# Xiao-SCD41-SSD1306.net
KiCad netlist of a schematic drawn in EAGLE
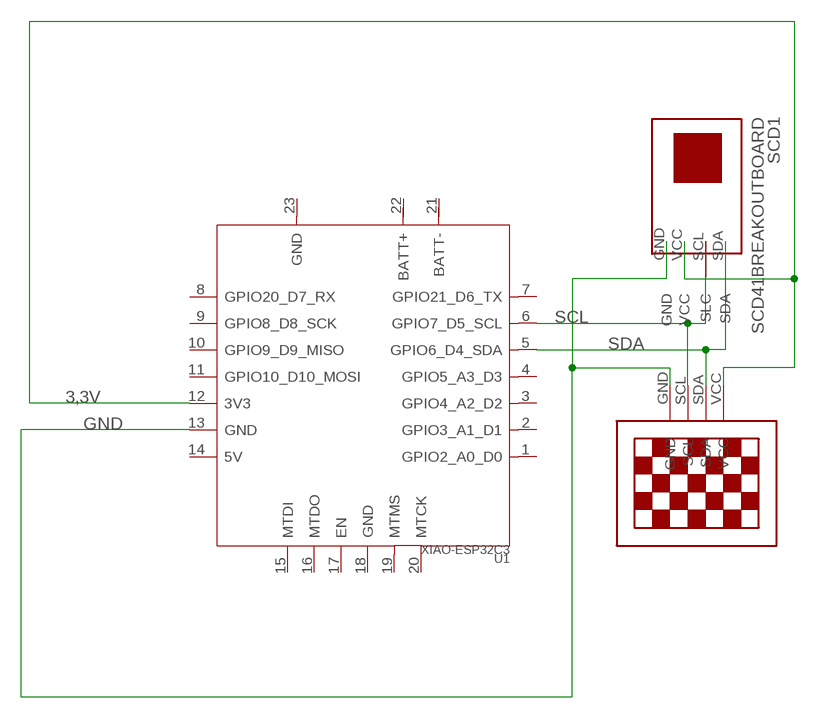
[diagram p0: schematic, sheet 1]

(export (version "E")
  (design (tool "Eeschema 10.0.6"))
  (components
    (comp (ref "SCD1")
      (value "SCD41BREAKOUTBOARD")
      (footprint "eagle-import:SCD41")
      (libsource (lib "eagle-import") (part "SCD41BREAKOUTBOARD"))
    )
    (comp (ref "U$1")
      (value "13\"OLED13\"OLED")
      (footprint "eagle-import:1.3_OLED")
      (libsource (lib "eagle-import") (part "13{dblquote}OLED13{dblquote}OLED"))
    )
    (comp (ref "U1")
      (value "XIAO-ESP32C3")
      (footprint "eagle-import:XIAO-ESP32C3-MODULE14P-2.54-21X17.8MM")
      (libsource (lib "eagle-import") (part "XIAO-ESP32C3"))
    )
  )
  (nets
    (net (code "1") (name "/3,3V") (class "Default")
      (node (ref "SCD1") (pin "VCC") (pinfunction "VCC_VCC") (pintype "bidirectional"))
      (node (ref "U$1") (pin "VCC") (pinfunction "VCC_VCC") (pintype "bidirectional"))
      (node (ref "U1") (pin "12") (pinfunction "3V3_12") (pintype "bidirectional"))
    )
    (net (code "2") (name "/GND") (class "Default")
      (node (ref "SCD1") (pin "GND") (pinfunction "GND_GND") (pintype "bidirectional"))
      (node (ref "U$1") (pin "GND") (pinfunction "GND_GND") (pintype "bidirectional"))
      (node (ref "U1") (pin "13") (pinfunction "GND_13") (pintype "bidirectional"))
    )
    (net (code "3") (name "/SCL") (class "Default")
      (node (ref "SCD1") (pin "SCL") (pinfunction "SLC_SCL") (pintype "bidirectional"))
      (node (ref "U$1") (pin "SCL") (pinfunction "SCL_SCL") (pintype "bidirectional"))
      (node (ref "U1") (pin "6") (pinfunction "GPIO7_D5_SCL_6") (pintype "bidirectional"))
    )
    (net (code "4") (name "/SDA") (class "Default")
      (node (ref "SCD1") (pin "SDA") (pinfunction "SDA_SDA") (pintype "bidirectional"))
      (node (ref "U$1") (pin "SDA") (pinfunction "SDA_SDA") (pintype "bidirectional"))
      (node (ref "U1") (pin "5") (pinfunction "GPIO6_D4_SDA_5") (pintype "bidirectional"))
    )
    (net (code "5") (name "unconnected-(U1-5V-Pad14)") (class "Default")
      (node (ref "U1") (pin "14") (pinfunction "5V_14") (pintype "bidirectional"))
    )
    (net (code "6") (name "unconnected-(U1-BATT+-Pad22)") (class "Default")
      (node (ref "U1") (pin "22") (pinfunction "BATT+_22") (pintype "bidirectional"))
    )
    (net (code "7") (name "unconnected-(U1-BATT--Pad21)") (class "Default")
      (node (ref "U1") (pin "21") (pinfunction "BATT-_21") (pintype "bidirectional"))
    )
    (net (code "8") (name "unconnected-(U1-EN-Pad17)") (class "Default")
      (node (ref "U1") (pin "17") (pinfunction "EN_17") (pintype "bidirectional"))
    )
    (net (code "9") (name "unconnected-(U1-GND-Pad18)") (class "Default")
      (node (ref "U1") (pin "18") (pinfunction "GND_18") (pintype "bidirectional"))
    )
    (net (code "10") (name "unconnected-(U1-GND-Pad23)") (class "Default")
      (node (ref "U1") (pin "23") (pinfunction "GND_23") (pintype "bidirectional"))
    )
    (net (code "11") (name "unconnected-(U1-GPIO2_A0_D0-Pad1)") (class "Default")
      (node (ref "U1") (pin "1") (pinfunction "GPIO2_A0_D0_1") (pintype "bidirectional"))
    )
    (net (code "12") (name "unconnected-(U1-GPIO3_A1_D1-Pad2)") (class "Default")
      (node (ref "U1") (pin "2") (pinfunction "GPIO3_A1_D1_2") (pintype "bidirectional"))
    )
    (net (code "13") (name "unconnected-(U1-GPIO4_A2_D2-Pad3)") (class "Default")
      (node (ref "U1") (pin "3") (pinfunction "GPIO4_A2_D2_3") (pintype "bidirectional"))
    )
    (net (code "14") (name "unconnected-(U1-GPIO5_A3_D3-Pad4)") (class "Default")
      (node (ref "U1") (pin "4") (pinfunction "GPIO5_A3_D3_4") (pintype "bidirectional"))
    )
    (net (code "15") (name "unconnected-(U1-GPIO8_D8_SCK-Pad9)") (class "Default")
      (node (ref "U1") (pin "9") (pinfunction "GPIO8_D8_SCK_9") (pintype "bidirectional"))
    )
    (net (code "16") (name "unconnected-(U1-GPIO9_D9_MISO-Pad10)") (class "Default")
      (node (ref "U1") (pin "10") (pinfunction "GPIO9_D9_MISO_10") (pintype "bidirectional"))
    )
    (net (code "17") (name "unconnected-(U1-GPIO10_D10_MOSI-Pad11)") (class "Default")
      (node (ref "U1") (pin "11") (pinfunction "GPIO10_D10_MOSI_11") (pintype "bidirectional"))
    )
    (net (code "18") (name "unconnected-(U1-GPIO20_D7_RX-Pad8)") (class "Default")
      (node (ref "U1") (pin "8") (pinfunction "GPIO20_D7_RX_8") (pintype "bidirectional"))
    )
    (net (code "19") (name "unconnected-(U1-GPIO21_D6_TX-Pad7)") (class "Default")
      (node (ref "U1") (pin "7") (pinfunction "GPIO21_D6_TX_7") (pintype "bidirectional"))
    )
    (net (code "20") (name "unconnected-(U1-MTCK-Pad20)") (class "Default")
      (node (ref "U1") (pin "20") (pinfunction "MTCK_20") (pintype "bidirectional"))
    )
    (net (code "21") (name "unconnected-(U1-MTDI-Pad15)") (class "Default")
      (node (ref "U1") (pin "15") (pinfunction "MTDI_15") (pintype "bidirectional"))
    )
    (net (code "22") (name "unconnected-(U1-MTDO-Pad16)") (class "Default")
      (node (ref "U1") (pin "16") (pinfunction "MTDO_16") (pintype "bidirectional"))
    )
    (net (code "23") (name "unconnected-(U1-MTMS-Pad19)") (class "Default")
      (node (ref "U1") (pin "19") (pinfunction "MTMS_19") (pintype "bidirectional"))
    )
  )
)
